# MCU-CTRLA.net
KiCad netlist of a schematic drawn in Altium Designer
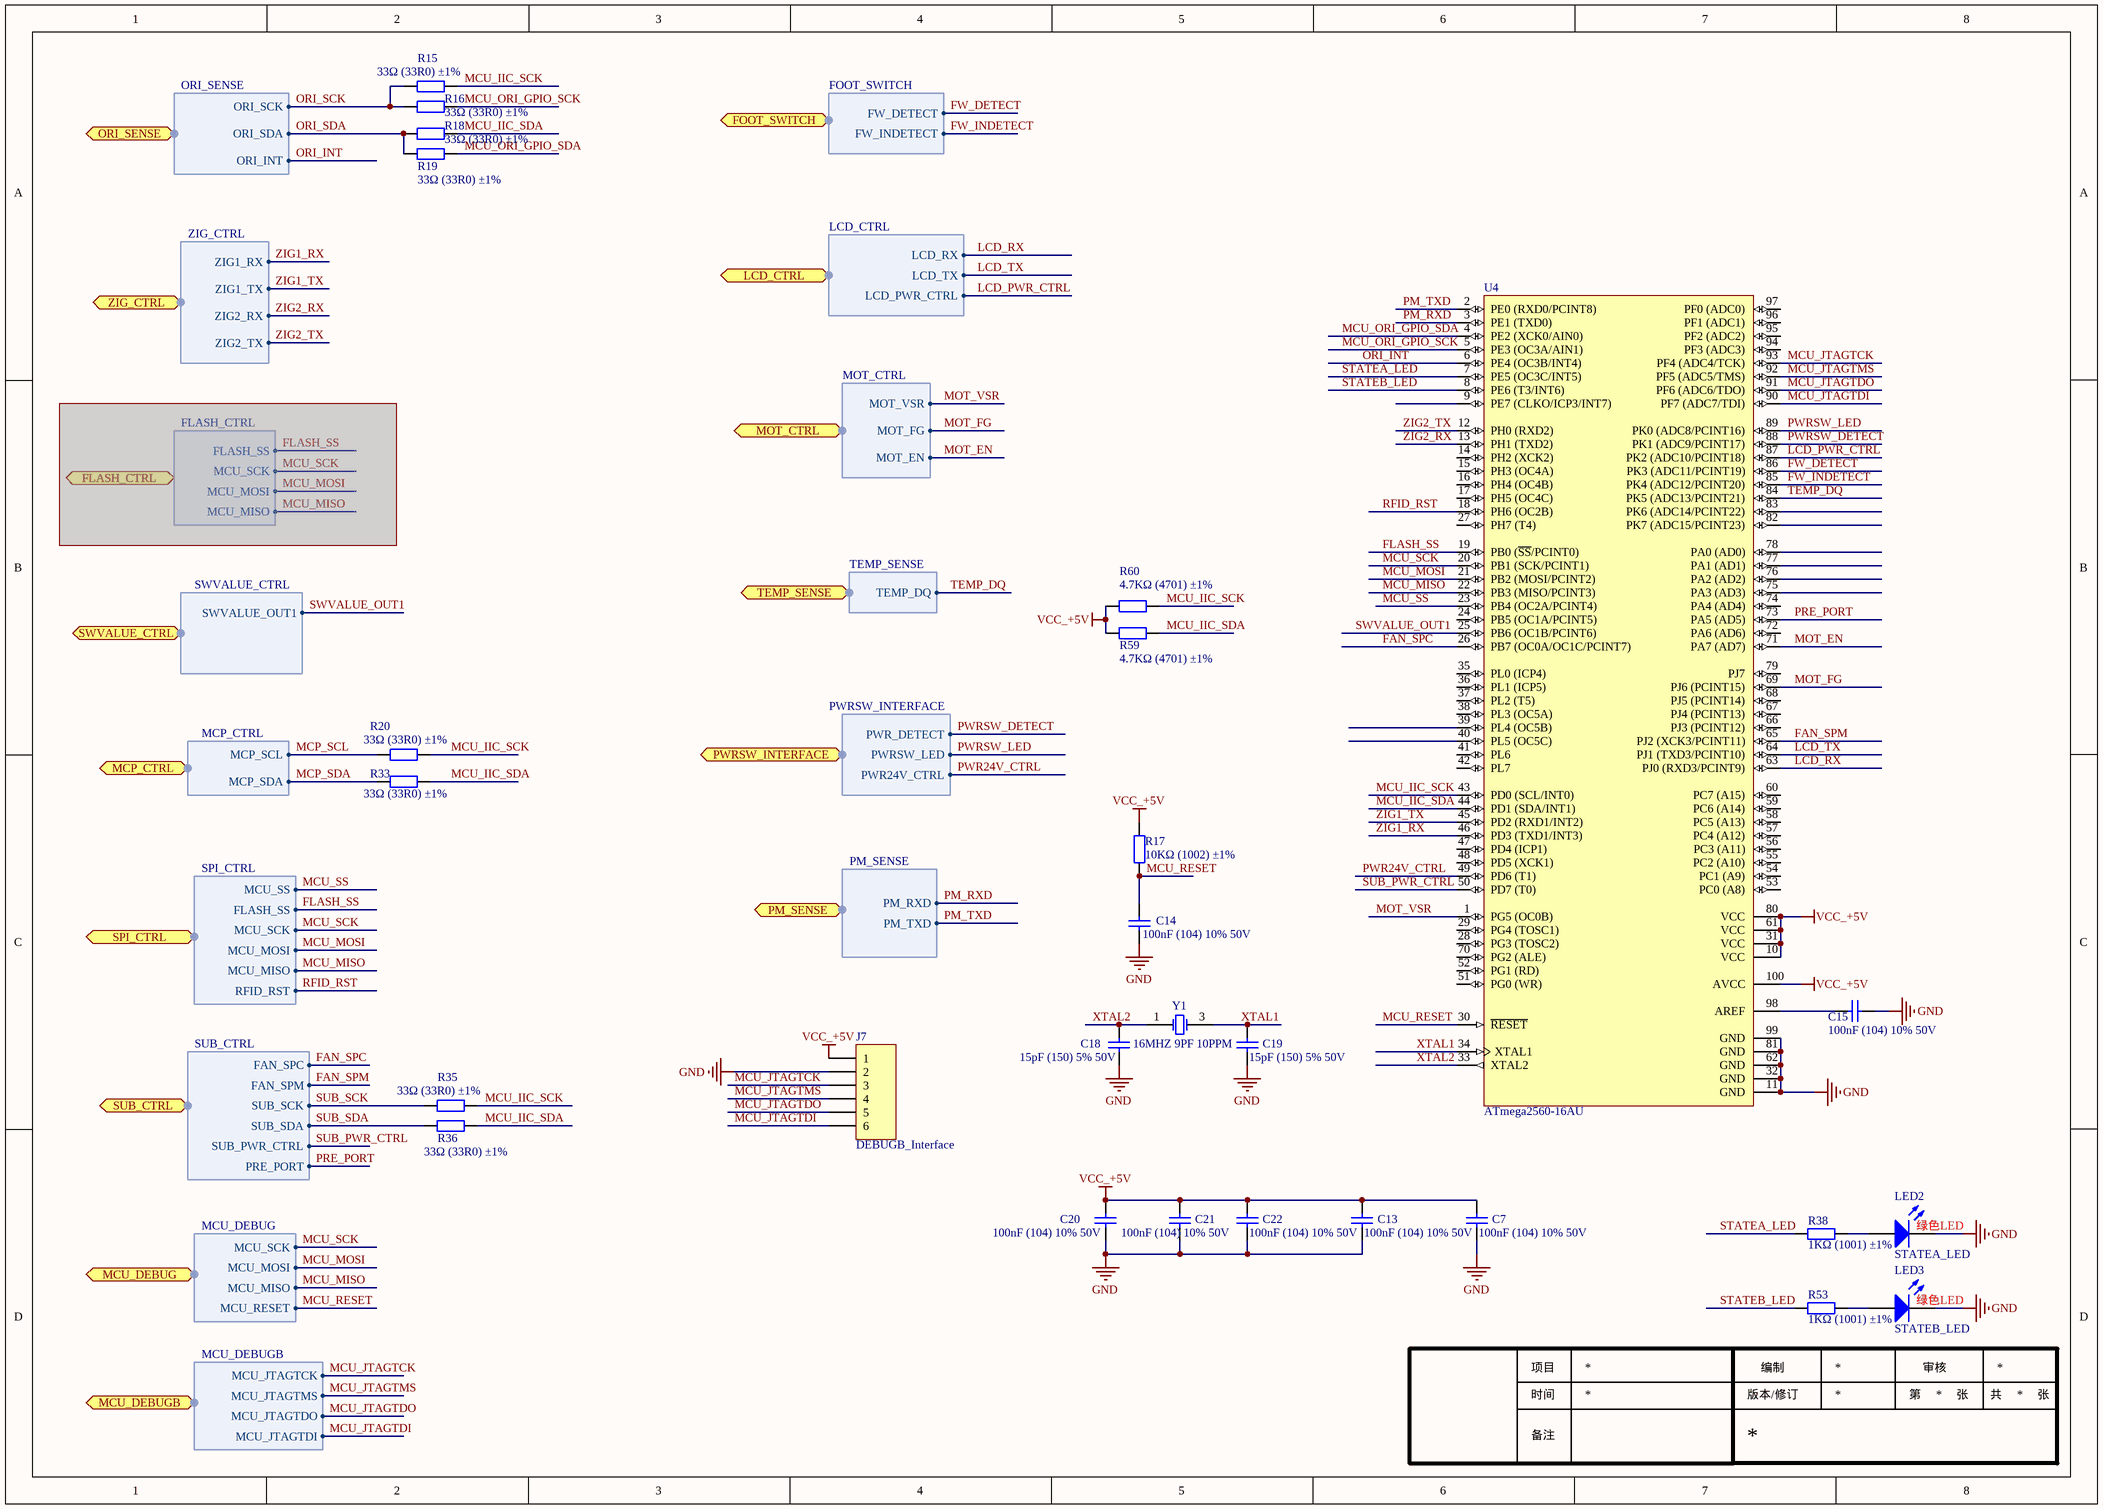
[diagram p0: MCU-CTRLA.SchDoc]

(export (version "E")
  (design (tool "Eeschema 10.0.6"))
  (components
    (comp (ref "C7")
      (value "100nF (104) 10% 50V")
      (footprint "LC-0603_C")
      (description "贴片电容")
      (libsource (lib "Miscellaneous Devices LC") (part "0603 100nF (104) 10% 50V"))
    )
    (comp (ref "C13")
      (value "100nF (104) 10% 50V")
      (footprint "LC-0603_C")
      (description "贴片电容")
      (libsource (lib "Miscellaneous Devices LC") (part "0603 100nF (104) 10% 50V"))
    )
    (comp (ref "C14")
      (value "100nF (104) 10% 50V")
      (footprint "LC-0603_C")
      (description "贴片电容")
      (libsource (lib "Miscellaneous Devices LC") (part "0603 100nF (104) 10% 50V"))
    )
    (comp (ref "C15")
      (value "100nF (104) 10% 50V")
      (footprint "LC-0603_C")
      (description "贴片电容")
      (libsource (lib "Miscellaneous Devices LC") (part "0603 100nF (104) 10% 50V"))
    )
    (comp (ref "C18")
      (value "15pF (150) 5% 50V")
      (footprint "LC-0603_C")
      (description "贴片电容")
      (libsource (lib "Miscellaneous Devices LC") (part "0603 15pF (150) 5% 50V"))
    )
    (comp (ref "C19")
      (value "15pF (150) 5% 50V")
      (footprint "LC-0603_C")
      (description "贴片电容")
      (libsource (lib "Miscellaneous Devices LC") (part "0603 15pF (150) 5% 50V"))
    )
    (comp (ref "C20")
      (value "100nF (104) 10% 50V")
      (footprint "LC-0603_C")
      (description "贴片电容")
      (libsource (lib "Miscellaneous Devices LC") (part "0603 100nF (104) 10% 50V"))
    )
    (comp (ref "C21")
      (value "100nF (104) 10% 50V")
      (footprint "LC-0603_C")
      (description "贴片电容")
      (libsource (lib "Miscellaneous Devices LC") (part "0603 100nF (104) 10% 50V"))
    )
    (comp (ref "C22")
      (value "100nF (104) 10% 50V")
      (footprint "LC-0603_C")
      (description "贴片电容")
      (libsource (lib "Miscellaneous Devices LC") (part "0603 100nF (104) 10% 50V"))
    )
    (comp (ref "J7")
      (value "DEBUGB_Interface")
      (footprint "MHDR1X6")
      (description "Header, 6-Pin")
      (fields (field (name "PUBLISHER") "Altium Limited"))
      (libsource (lib "Miscellaneous Connectors") (part "MHDR1X6"))
    )
    (comp (ref "LED2")
      (value "STATEA_LED")
      (footprint "LC-0603_LED_S1")
      (libsource (lib "Altium_schematic_lib") (part "LEDA"))
    )
    (comp (ref "LED3")
      (value "STATEB_LED")
      (footprint "LC-0603_LED_S1")
      (libsource (lib "Altium_schematic_lib") (part "LEDA"))
    )
    (comp (ref "R15")
      (value "33Ω (33R0) ±1%")
      (footprint "LC-0603_R")
      (description "贴片电阻")
      (libsource (lib "Miscellaneous Devices LC") (part "0603 33Ω (33R0) 1%"))
    )
    (comp (ref "R16")
      (value "33Ω (33R0) ±1%")
      (footprint "LC-0603_R")
      (description "贴片电阻")
      (libsource (lib "Miscellaneous Devices LC") (part "0603 33Ω (33R0) 1%"))
    )
    (comp (ref "R17")
      (value "10KΩ (1002) ±1%")
      (footprint "LC-0603_R")
      (description "贴片电阻")
      (libsource (lib "Miscellaneous Devices LC") (part "0603 10KΩ (1002) 1%"))
    )
    (comp (ref "R18")
      (value "33Ω (33R0) ±1%")
      (footprint "LC-0603_R")
      (description "贴片电阻")
      (libsource (lib "Miscellaneous Devices LC") (part "0603 33Ω (33R0) 1%"))
    )
    (comp (ref "R19")
      (value "33Ω (33R0) ±1%")
      (footprint "LC-0603_R")
      (description "贴片电阻")
      (libsource (lib "Miscellaneous Devices LC") (part "0603 33Ω (33R0) 1%"))
    )
    (comp (ref "R20")
      (value "33Ω (33R0) ±1%")
      (footprint "LC-0603_R")
      (description "贴片电阻")
      (libsource (lib "Miscellaneous Devices LC") (part "0603 33Ω (33R0) 1%"))
    )
    (comp (ref "R33")
      (value "33Ω (33R0) ±1%")
      (footprint "LC-0603_R")
      (description "贴片电阻")
      (libsource (lib "Miscellaneous Devices LC") (part "0603 33Ω (33R0) 1%"))
    )
    (comp (ref "R35")
      (value "33Ω (33R0) ±1%")
      (footprint "LC-0603_R")
      (description "贴片电阻")
      (libsource (lib "Miscellaneous Devices LC") (part "0603 33Ω (33R0) 1%"))
    )
    (comp (ref "R36")
      (value "33Ω (33R0) ±1%")
      (footprint "LC-0603_R")
      (description "贴片电阻")
      (libsource (lib "Miscellaneous Devices LC") (part "0603 33Ω (33R0) 1%"))
    )
    (comp (ref "R38")
      (value "1KΩ (1001) ±1%")
      (footprint "LC-0603_R")
      (description "贴片电阻")
      (libsource (lib "Miscellaneous Devices LC") (part "0603 1KΩ (1001) 1%"))
    )
    (comp (ref "R53")
      (value "1KΩ (1001) ±1%")
      (footprint "LC-0603_R")
      (description "贴片电阻")
      (libsource (lib "Miscellaneous Devices LC") (part "0603 1KΩ (1001) 1%"))
    )
    (comp (ref "R59")
      (value "4.7KΩ (4701) ±1%")
      (footprint "LC-0603_R")
      (description "贴片电阻")
      (libsource (lib "Miscellaneous Devices LC") (part "0603 4.7KΩ (4701) 1%"))
    )
    (comp (ref "R60")
      (value "4.7KΩ (4701) ±1%")
      (footprint "LC-0603_R")
      (description "贴片电阻")
      (libsource (lib "Miscellaneous Devices LC") (part "0603 4.7KΩ (4701) 1%"))
    )
    (comp (ref "U4")
      (value "ATmega2560-16AU")
      (footprint "100A_N")
      (libsource (lib "Atmel Microcontroller megaAVR") (part "ATmega2560-16AU"))
    )
    (comp (ref "Y1")
      (value "16MHZ 9PF 10PPM")
      (footprint "LC-SMD-3225_4P")
      (description "贴片晶振")
      (libsource (lib "Miscellaneous Devices LC") (part "SMD-3225_4P  16MHZ 9PF 10PPM"))
    )
  )
  (nets
    (net (code "16") (name "/FAN_SPC") (class "Default")
      (node (ref "U4") (pin "26") (pinfunction "PB7_(OC0A/OC1C/PCINT7)_26") (pintype "bidirectional"))
    )
    (net (code "17") (name "/FAN_SPM") (class "Default")
      (node (ref "U4") (pin "65") (pinfunction "PJ2_(XCK3/PCINT11)_65") (pintype "bidirectional"))
    )
    (net (code "18") (name "/FLASH_SS") (class "Default")
      (node (ref "U4") (pin "19") (pinfunction "PB0_(~{SS}/PCINT0)_19") (pintype "bidirectional"))
    )
    (net (code "19") (name "/FW_DETECT") (class "Default")
      (node (ref "U4") (pin "86") (pinfunction "PK3_(ADC11/PCINT19)_86") (pintype "bidirectional"))
    )
    (net (code "20") (name "/FW_INDETECT") (class "Default")
      (node (ref "U4") (pin "85") (pinfunction "PK4_(ADC12/PCINT20)_85") (pintype "bidirectional"))
    )
    (net (code "21") (name "/LCD_PWR_CTRL") (class "Default")
      (node (ref "U4") (pin "87") (pinfunction "PK2_(ADC10/PCINT18)_87") (pintype "bidirectional"))
    )
    (net (code "22") (name "/LCD_RX") (class "Default")
      (node (ref "U4") (pin "63") (pinfunction "PJ0_(RXD3/PCINT9)_63") (pintype "bidirectional"))
    )
    (net (code "23") (name "/LCD_TX") (class "Default")
      (node (ref "U4") (pin "64") (pinfunction "PJ1_(TXD3/PCINT10)_64") (pintype "bidirectional"))
    )
    (net (code "24") (name "/MCP_SCL") (class "Default")
      (node (ref "R20") (pin "1") (pinfunction "1_1") (pintype "passive"))
    )
    (net (code "25") (name "/MCP_SDA") (class "Default")
      (node (ref "R33") (pin "1") (pinfunction "1_1") (pintype "passive"))
    )
    (net (code "26") (name "/MCU_IIC_SCK") (class "Default")
      (node (ref "R15") (pin "2") (pinfunction "2_2") (pintype "passive"))
      (node (ref "R20") (pin "2") (pinfunction "2_2") (pintype "passive"))
      (node (ref "R35") (pin "2") (pinfunction "2_2") (pintype "passive"))
      (node (ref "R60") (pin "1") (pinfunction "1_1") (pintype "passive"))
      (node (ref "U4") (pin "43") (pinfunction "PD0_(SCL/INT0)_43") (pintype "bidirectional"))
    )
    (net (code "27") (name "/MCU_IIC_SDA") (class "Default")
      (node (ref "R18") (pin "2") (pinfunction "2_2") (pintype "passive"))
      (node (ref "R33") (pin "2") (pinfunction "2_2") (pintype "passive"))
      (node (ref "R36") (pin "2") (pinfunction "2_2") (pintype "passive"))
      (node (ref "R59") (pin "1") (pinfunction "1_1") (pintype "passive"))
      (node (ref "U4") (pin "44") (pinfunction "PD1_(SDA/INT1)_44") (pintype "bidirectional"))
    )
    (net (code "28") (name "/MCU_JTAGTCK") (class "Default")
      (node (ref "J7") (pin "3") (pinfunction "3_3") (pintype "passive"))
      (node (ref "U4") (pin "93") (pinfunction "PF4_(ADC4/TCK)_93") (pintype "bidirectional"))
    )
    (net (code "29") (name "/MCU_JTAGTDI") (class "Default")
      (node (ref "J7") (pin "6") (pinfunction "6_6") (pintype "passive"))
      (node (ref "U4") (pin "90") (pinfunction "PF7_(ADC7/TDI)_90") (pintype "bidirectional"))
    )
    (net (code "30") (name "/MCU_JTAGTDO") (class "Default")
      (node (ref "J7") (pin "5") (pinfunction "5_5") (pintype "passive"))
      (node (ref "U4") (pin "91") (pinfunction "PF6_(ADC6/TDO)_91") (pintype "bidirectional"))
    )
    (net (code "31") (name "/MCU_JTAGTMS") (class "Default")
      (node (ref "J7") (pin "4") (pinfunction "4_4") (pintype "passive"))
      (node (ref "U4") (pin "92") (pinfunction "PF5_(ADC5/TMS)_92") (pintype "bidirectional"))
    )
    (net (code "32") (name "/MCU_MISO") (class "Default")
      (node (ref "U4") (pin "22") (pinfunction "PB3_(MISO/PCINT3)_22") (pintype "bidirectional"))
    )
    (net (code "33") (name "/MCU_MOSI") (class "Default")
      (node (ref "U4") (pin "21") (pinfunction "PB2_(MOSI/PCINT2)_21") (pintype "bidirectional"))
    )
    (net (code "34") (name "/MCU_ORI_GPIO_SCK") (class "Default")
      (node (ref "R16") (pin "2") (pinfunction "2_2") (pintype "passive"))
      (node (ref "U4") (pin "5") (pinfunction "PE3_(OC3A/AIN1)_5") (pintype "bidirectional"))
    )
    (net (code "35") (name "/MCU_ORI_GPIO_SDA") (class "Default")
      (node (ref "R19") (pin "2") (pinfunction "2_2") (pintype "passive"))
      (node (ref "U4") (pin "4") (pinfunction "PE2_(XCK0/AIN0)_4") (pintype "bidirectional"))
    )
    (net (code "36") (name "/MCU_RESET") (class "Default")
      (node (ref "C14") (pin "2") (pinfunction "2_2") (pintype "passive"))
      (node (ref "R17") (pin "1") (pinfunction "1_1") (pintype "passive"))
      (node (ref "U4") (pin "30") (pinfunction "~{RESET}_30") (pintype "input"))
    )
    (net (code "37") (name "/MCU_SCK") (class "Default")
      (node (ref "U4") (pin "20") (pinfunction "PB1_(SCK/PCINT1)_20") (pintype "bidirectional"))
    )
    (net (code "38") (name "/MCU_SS") (class "Default")
      (node (ref "U4") (pin "23") (pinfunction "PB4_(OC2A/PCINT4)_23") (pintype "bidirectional"))
    )
    (net (code "39") (name "/MOT_EN") (class "Default")
      (node (ref "U4") (pin "71") (pinfunction "PA7_(AD7)_71") (pintype "bidirectional"))
    )
    (net (code "40") (name "/MOT_FG") (class "Default")
      (node (ref "U4") (pin "69") (pinfunction "PJ6_(PCINT15)_69") (pintype "bidirectional"))
    )
    (net (code "41") (name "/MOT_VSR") (class "Default")
      (node (ref "U4") (pin "1") (pinfunction "PG5_(OC0B)_1") (pintype "bidirectional"))
    )
    (net (code "42") (name "/ORI_INT") (class "Default")
      (node (ref "U4") (pin "6") (pinfunction "PE4_(OC3B/INT4)_6") (pintype "bidirectional"))
    )
    (net (code "43") (name "/ORI_SCK") (class "Default")
      (node (ref "R15") (pin "1") (pinfunction "1_1") (pintype "passive"))
      (node (ref "R16") (pin "1") (pinfunction "1_1") (pintype "passive"))
    )
    (net (code "44") (name "/ORI_SDA") (class "Default")
      (node (ref "R18") (pin "1") (pinfunction "1_1") (pintype "passive"))
      (node (ref "R19") (pin "1") (pinfunction "1_1") (pintype "passive"))
    )
    (net (code "45") (name "/PM_RXD") (class "Default")
      (node (ref "U4") (pin "3") (pinfunction "PE1_(TXD0)_3") (pintype "bidirectional"))
    )
    (net (code "46") (name "/PM_TXD") (class "Default")
      (node (ref "U4") (pin "2") (pinfunction "PE0_(RXD0/PCINT8)_2") (pintype "bidirectional"))
    )
    (net (code "47") (name "/PRE_PORT") (class "Default")
      (node (ref "U4") (pin "73") (pinfunction "PA5_(AD5)_73") (pintype "bidirectional"))
    )
    (net (code "48") (name "/PWR24V_CTRL") (class "Default")
      (node (ref "U4") (pin "49") (pinfunction "PD6_(T1)_49") (pintype "bidirectional"))
    )
    (net (code "49") (name "/PWRSW_DETECT") (class "Default")
      (node (ref "U4") (pin "88") (pinfunction "PK1_(ADC9/PCINT17)_88") (pintype "bidirectional"))
    )
    (net (code "50") (name "/PWRSW_LED") (class "Default")
      (node (ref "U4") (pin "89") (pinfunction "PK0_(ADC8/PCINT16)_89") (pintype "bidirectional"))
    )
    (net (code "51") (name "/RFID_RST") (class "Default")
      (node (ref "U4") (pin "18") (pinfunction "PH6_(OC2B)_18") (pintype "bidirectional"))
    )
    (net (code "52") (name "/STATEA_LED") (class "Default")
      (node (ref "R38") (pin "1") (pinfunction "1_1") (pintype "passive"))
      (node (ref "U4") (pin "7") (pinfunction "PE5_(OC3C/INT5)_7") (pintype "bidirectional"))
    )
    (net (code "53") (name "/STATEB_LED") (class "Default")
      (node (ref "R53") (pin "1") (pinfunction "1_1") (pintype "passive"))
      (node (ref "U4") (pin "8") (pinfunction "PE6_(T3/INT6)_8") (pintype "bidirectional"))
    )
    (net (code "54") (name "/SUB_PWR_CTRL") (class "Default")
      (node (ref "U4") (pin "50") (pinfunction "PD7_(T0)_50") (pintype "bidirectional"))
    )
    (net (code "55") (name "/SUB_SCK") (class "Default")
      (node (ref "R35") (pin "1") (pinfunction "1_1") (pintype "passive"))
    )
    (net (code "56") (name "/SUB_SDA") (class "Default")
      (node (ref "R36") (pin "1") (pinfunction "1_1") (pintype "passive"))
    )
    (net (code "57") (name "/SWVALUE_OUT1") (class "Default")
      (node (ref "U4") (pin "25") (pinfunction "PB6_(OC1B/PCINT6)_25") (pintype "bidirectional"))
    )
    (net (code "58") (name "/TEMP_DQ") (class "Default")
      (node (ref "U4") (pin "84") (pinfunction "PK5_(ADC13/PCINT21)_84") (pintype "bidirectional"))
    )
    (net (code "59") (name "/XTAL1") (class "Default")
      (node (ref "C19") (pin "2") (pinfunction "2_2") (pintype "passive"))
      (node (ref "U4") (pin "34") (pinfunction "XTAL1_34") (pintype "input"))
      (node (ref "Y1") (pin "3") (pinfunction "OSC2_3") (pintype "passive"))
    )
    (net (code "60") (name "/XTAL2") (class "Default")
      (node (ref "C18") (pin "2") (pinfunction "2_2") (pintype "passive"))
      (node (ref "U4") (pin "33") (pinfunction "XTAL2_33") (pintype "output"))
      (node (ref "Y1") (pin "1") (pinfunction "OSC1_1") (pintype "passive"))
    )
    (net (code "61") (name "/ZIG1_RX") (class "Default")
      (node (ref "U4") (pin "46") (pinfunction "PD3_(TXD1/INT3)_46") (pintype "bidirectional"))
    )
    (net (code "62") (name "/ZIG1_TX") (class "Default")
      (node (ref "U4") (pin "45") (pinfunction "PD2_(RXD1/INT2)_45") (pintype "bidirectional"))
    )
    (net (code "63") (name "/ZIG2_RX") (class "Default")
      (node (ref "U4") (pin "13") (pinfunction "PH1_(TXD2)_13") (pintype "bidirectional"))
    )
    (net (code "64") (name "/ZIG2_TX") (class "Default")
      (node (ref "U4") (pin "12") (pinfunction "PH0_(RXD2)_12") (pintype "bidirectional"))
    )
    (net (code "80") (name "GND") (class "Default")
      (node (ref "C13") (pin "1") (pinfunction "1_1") (pintype "passive"))
      (node (ref "C14") (pin "1") (pinfunction "1_1") (pintype "passive"))
      (node (ref "C15") (pin "1") (pinfunction "1_1") (pintype "passive"))
      (node (ref "C18") (pin "1") (pinfunction "1_1") (pintype "passive"))
      (node (ref "C19") (pin "1") (pinfunction "1_1") (pintype "passive"))
      (node (ref "C20") (pin "1") (pinfunction "1_1") (pintype "passive"))
      (node (ref "C21") (pin "1") (pinfunction "1_1") (pintype "passive"))
      (node (ref "C22") (pin "1") (pinfunction "1_1") (pintype "passive"))
      (node (ref "C7") (pin "1") (pinfunction "1_1") (pintype "passive"))
      (node (ref "J7") (pin "2") (pinfunction "2_2") (pintype "passive"))
      (node (ref "LED2") (pin "K") (pinfunction "K_K") (pintype "passive"))
      (node (ref "LED3") (pin "K") (pinfunction "K_K") (pintype "passive"))
      (node (ref "U4") (pin "11") (pinfunction "GND_11") (pintype "power_in"))
      (node (ref "U4") (pin "32") (pinfunction "GND_32") (pintype "power_in"))
      (node (ref "U4") (pin "62") (pinfunction "GND_62") (pintype "power_in"))
      (node (ref "U4") (pin "81") (pinfunction "GND_81") (pintype "power_in"))
      (node (ref "U4") (pin "99") (pinfunction "GND_99") (pintype "power_in"))
    )
    (net (code "81") (name "Net-(LED2-PadA)") (class "Default")
      (node (ref "LED2") (pin "A") (pinfunction "A_A") (pintype "passive"))
      (node (ref "R38") (pin "2") (pinfunction "2_2") (pintype "passive"))
    )
    (net (code "82") (name "Net-(LED3-PadA)") (class "Default")
      (node (ref "LED3") (pin "A") (pinfunction "A_A") (pintype "passive"))
      (node (ref "R53") (pin "2") (pinfunction "2_2") (pintype "passive"))
    )
    (net (code "83") (name "Net-(U4-AREF)") (class "Default")
      (node (ref "C15") (pin "2") (pinfunction "2_2") (pintype "passive"))
      (node (ref "U4") (pin "98") (pinfunction "AREF_98") (pintype "power_in"))
    )
    (net (code "84") (name "VCC_+5V") (class "Default")
      (node (ref "C13") (pin "2") (pinfunction "2_2") (pintype "passive"))
      (node (ref "C20") (pin "2") (pinfunction "2_2") (pintype "passive"))
      (node (ref "C21") (pin "2") (pinfunction "2_2") (pintype "passive"))
      (node (ref "C22") (pin "2") (pinfunction "2_2") (pintype "passive"))
      (node (ref "C7") (pin "2") (pinfunction "2_2") (pintype "passive"))
      (node (ref "J7") (pin "1") (pinfunction "1_1") (pintype "passive"))
      (node (ref "R17") (pin "2") (pinfunction "2_2") (pintype "passive"))
      (node (ref "R59") (pin "2") (pinfunction "2_2") (pintype "passive"))
      (node (ref "R60") (pin "2") (pinfunction "2_2") (pintype "passive"))
      (node (ref "U4") (pin "10") (pinfunction "VCC_10") (pintype "power_in"))
      (node (ref "U4") (pin "100") (pinfunction "AVCC_100") (pintype "power_in"))
      (node (ref "U4") (pin "31") (pinfunction "VCC_31") (pintype "power_in"))
      (node (ref "U4") (pin "61") (pinfunction "VCC_61") (pintype "power_in"))
      (node (ref "U4") (pin "80") (pinfunction "VCC_80") (pintype "power_in"))
    )
    (net (code "85") (name "unconnected-(U4-PA0_(AD0)-Pad78)") (class "Default")
      (node (ref "U4") (pin "78") (pinfunction "PA0_(AD0)_78") (pintype "bidirectional"))
    )
    (net (code "86") (name "unconnected-(U4-PA1_(AD1)-Pad77)") (class "Default")
      (node (ref "U4") (pin "77") (pinfunction "PA1_(AD1)_77") (pintype "bidirectional"))
    )
    (net (code "87") (name "unconnected-(U4-PA2_(AD2)-Pad76)") (class "Default")
      (node (ref "U4") (pin "76") (pinfunction "PA2_(AD2)_76") (pintype "bidirectional"))
    )
    (net (code "88") (name "unconnected-(U4-PA3_(AD3)-Pad75)") (class "Default")
      (node (ref "U4") (pin "75") (pinfunction "PA3_(AD3)_75") (pintype "bidirectional"))
    )
    (net (code "89") (name "unconnected-(U4-PA4_(AD4)-Pad74)") (class "Default")
      (node (ref "U4") (pin "74") (pinfunction "PA4_(AD4)_74") (pintype "bidirectional"))
    )
    (net (code "90") (name "unconnected-(U4-PA6_(AD6)-Pad72)") (class "Default")
      (node (ref "U4") (pin "72") (pinfunction "PA6_(AD6)_72") (pintype "bidirectional"))
    )
    (net (code "91") (name "unconnected-(U4-PB5_(OC1A{slash}PCINT5)-Pad24)") (class "Default")
      (node (ref "U4") (pin "24") (pinfunction "PB5_(OC1A/PCINT5)_24") (pintype "bidirectional"))
    )
    (net (code "92") (name "unconnected-(U4-PC0_(A8)-Pad53)") (class "Default")
      (node (ref "U4") (pin "53") (pinfunction "PC0_(A8)_53") (pintype "bidirectional"))
    )
    (net (code "93") (name "unconnected-(U4-PC1_(A9)-Pad54)") (class "Default")
      (node (ref "U4") (pin "54") (pinfunction "PC1_(A9)_54") (pintype "bidirectional"))
    )
    (net (code "94") (name "unconnected-(U4-PC2_(A10)-Pad55)") (class "Default")
      (node (ref "U4") (pin "55") (pinfunction "PC2_(A10)_55") (pintype "bidirectional"))
    )
    (net (code "95") (name "unconnected-(U4-PC3_(A11)-Pad56)") (class "Default")
      (node (ref "U4") (pin "56") (pinfunction "PC3_(A11)_56") (pintype "bidirectional"))
    )
    (net (code "96") (name "unconnected-(U4-PC4_(A12)-Pad57)") (class "Default")
      (node (ref "U4") (pin "57") (pinfunction "PC4_(A12)_57") (pintype "bidirectional"))
    )
    (net (code "97") (name "unconnected-(U4-PC5_(A13)-Pad58)") (class "Default")
      (node (ref "U4") (pin "58") (pinfunction "PC5_(A13)_58") (pintype "bidirectional"))
    )
    (net (code "98") (name "unconnected-(U4-PC6_(A14)-Pad59)") (class "Default")
      (node (ref "U4") (pin "59") (pinfunction "PC6_(A14)_59") (pintype "bidirectional"))
    )
    (net (code "99") (name "unconnected-(U4-PC7_(A15)-Pad60)") (class "Default")
      (node (ref "U4") (pin "60") (pinfunction "PC7_(A15)_60") (pintype "bidirectional"))
    )
    (net (code "100") (name "unconnected-(U4-PD4_(ICP1)-Pad47)") (class "Default")
      (node (ref "U4") (pin "47") (pinfunction "PD4_(ICP1)_47") (pintype "bidirectional"))
    )
    (net (code "101") (name "unconnected-(U4-PD5_(XCK1)-Pad48)") (class "Default")
      (node (ref "U4") (pin "48") (pinfunction "PD5_(XCK1)_48") (pintype "bidirectional"))
    )
    (net (code "102") (name "unconnected-(U4-PE7_(CLKO{slash}ICP3{slash}INT7)-Pad9)") (class "Default")
      (node (ref "U4") (pin "9") (pinfunction "PE7_(CLKO/ICP3/INT7)_9") (pintype "bidirectional"))
    )
    (net (code "103") (name "unconnected-(U4-PF0_(ADC0)-Pad97)") (class "Default")
      (node (ref "U4") (pin "97") (pinfunction "PF0_(ADC0)_97") (pintype "bidirectional"))
    )
    (net (code "104") (name "unconnected-(U4-PF1_(ADC1)-Pad96)") (class "Default")
      (node (ref "U4") (pin "96") (pinfunction "PF1_(ADC1)_96") (pintype "bidirectional"))
    )
    (net (code "105") (name "unconnected-(U4-PF2_(ADC2)-Pad95)") (class "Default")
      (node (ref "U4") (pin "95") (pinfunction "PF2_(ADC2)_95") (pintype "bidirectional"))
    )
    (net (code "106") (name "unconnected-(U4-PF3_(ADC3)-Pad94)") (class "Default")
      (node (ref "U4") (pin "94") (pinfunction "PF3_(ADC3)_94") (pintype "bidirectional"))
    )
    (net (code "107") (name "unconnected-(U4-PG0_(WR)-Pad51)") (class "Default")
      (node (ref "U4") (pin "51") (pinfunction "PG0_(WR)_51") (pintype "bidirectional"))
    )
    (net (code "108") (name "unconnected-(U4-PG1_(RD)-Pad52)") (class "Default")
      (node (ref "U4") (pin "52") (pinfunction "PG1_(RD)_52") (pintype "bidirectional"))
    )
    (net (code "109") (name "unconnected-(U4-PG2_(ALE)-Pad70)") (class "Default")
      (node (ref "U4") (pin "70") (pinfunction "PG2_(ALE)_70") (pintype "bidirectional"))
    )
    (net (code "110") (name "unconnected-(U4-PG3_(TOSC2)-Pad28)") (class "Default")
      (node (ref "U4") (pin "28") (pinfunction "PG3_(TOSC2)_28") (pintype "bidirectional"))
    )
    (net (code "111") (name "unconnected-(U4-PG4_(TOSC1)-Pad29)") (class "Default")
      (node (ref "U4") (pin "29") (pinfunction "PG4_(TOSC1)_29") (pintype "bidirectional"))
    )
    (net (code "112") (name "unconnected-(U4-PH2_(XCK2)-Pad14)") (class "Default")
      (node (ref "U4") (pin "14") (pinfunction "PH2_(XCK2)_14") (pintype "bidirectional"))
    )
    (net (code "113") (name "unconnected-(U4-PH3_(OC4A)-Pad15)") (class "Default")
      (node (ref "U4") (pin "15") (pinfunction "PH3_(OC4A)_15") (pintype "bidirectional"))
    )
    (net (code "114") (name "unconnected-(U4-PH4_(OC4B)-Pad16)") (class "Default")
      (node (ref "U4") (pin "16") (pinfunction "PH4_(OC4B)_16") (pintype "bidirectional"))
    )
    (net (code "115") (name "unconnected-(U4-PH5_(OC4C)-Pad17)") (class "Default")
      (node (ref "U4") (pin "17") (pinfunction "PH5_(OC4C)_17") (pintype "bidirectional"))
    )
    (net (code "116") (name "unconnected-(U4-PH7_(T4)-Pad27)") (class "Default")
      (node (ref "U4") (pin "27") (pinfunction "PH7_(T4)_27") (pintype "bidirectional"))
    )
    (net (code "117") (name "unconnected-(U4-PJ3_(PCINT12)-Pad66)") (class "Default")
      (node (ref "U4") (pin "66") (pinfunction "PJ3_(PCINT12)_66") (pintype "bidirectional"))
    )
    (net (code "118") (name "unconnected-(U4-PJ4_(PCINT13)-Pad67)") (class "Default")
      (node (ref "U4") (pin "67") (pinfunction "PJ4_(PCINT13)_67") (pintype "bidirectional"))
    )
    (net (code "119") (name "unconnected-(U4-PJ5_(PCINT14)-Pad68)") (class "Default")
      (node (ref "U4") (pin "68") (pinfunction "PJ5_(PCINT14)_68") (pintype "bidirectional"))
    )
    (net (code "120") (name "unconnected-(U4-PJ7-Pad79)") (class "Default")
      (node (ref "U4") (pin "79") (pinfunction "PJ7_79") (pintype "bidirectional"))
    )
    (net (code "121") (name "unconnected-(U4-PK6_(ADC14{slash}PCINT22)-Pad83)") (class "Default")
      (node (ref "U4") (pin "83") (pinfunction "PK6_(ADC14/PCINT22)_83") (pintype "bidirectional"))
    )
    (net (code "122") (name "unconnected-(U4-PK7_(ADC15{slash}PCINT23)-Pad82)") (class "Default")
      (node (ref "U4") (pin "82") (pinfunction "PK7_(ADC15/PCINT23)_82") (pintype "bidirectional"))
    )
    (net (code "123") (name "unconnected-(U4-PL0_(ICP4)-Pad35)") (class "Default")
      (node (ref "U4") (pin "35") (pinfunction "PL0_(ICP4)_35") (pintype "bidirectional"))
    )
    (net (code "124") (name "unconnected-(U4-PL1_(ICP5)-Pad36)") (class "Default")
      (node (ref "U4") (pin "36") (pinfunction "PL1_(ICP5)_36") (pintype "bidirectional"))
    )
    (net (code "125") (name "unconnected-(U4-PL2_(T5)-Pad37)") (class "Default")
      (node (ref "U4") (pin "37") (pinfunction "PL2_(T5)_37") (pintype "bidirectional"))
    )
    (net (code "126") (name "unconnected-(U4-PL3_(OC5A)-Pad38)") (class "Default")
      (node (ref "U4") (pin "38") (pinfunction "PL3_(OC5A)_38") (pintype "bidirectional"))
    )
    (net (code "127") (name "unconnected-(U4-PL4_(OC5B)-Pad39)") (class "Default")
      (node (ref "U4") (pin "39") (pinfunction "PL4_(OC5B)_39") (pintype "bidirectional"))
    )
    (net (code "128") (name "unconnected-(U4-PL5_(OC5C)-Pad40)") (class "Default")
      (node (ref "U4") (pin "40") (pinfunction "PL5_(OC5C)_40") (pintype "bidirectional"))
    )
    (net (code "129") (name "unconnected-(U4-PL6-Pad41)") (class "Default")
      (node (ref "U4") (pin "41") (pinfunction "PL6_41") (pintype "bidirectional"))
    )
    (net (code "130") (name "unconnected-(U4-PL7-Pad42)") (class "Default")
      (node (ref "U4") (pin "42") (pinfunction "PL7_42") (pintype "bidirectional"))
    )
  )
)
